# Soft_Latch_11082021.net
KiCad netlist of a schematic drawn in Altium Designer
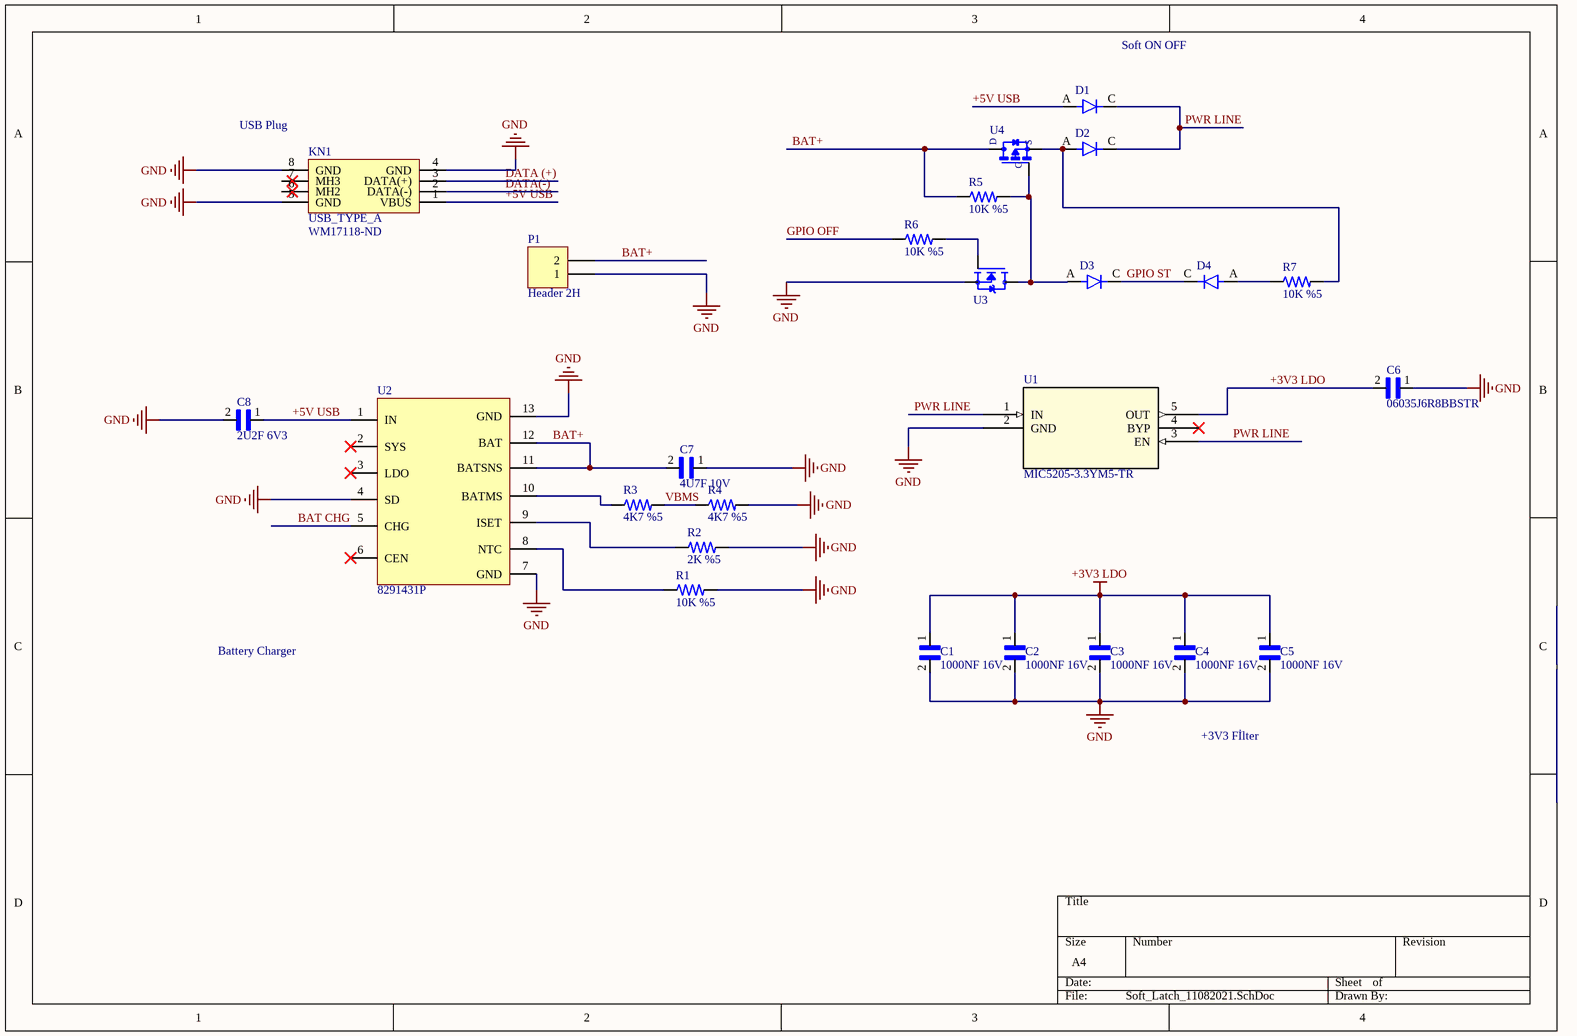
[diagram p0: Soft_Latch_11082021.SchDoc]

(export (version "E")
  (design (tool "Eeschema 10.0.6"))
  (components
    (comp (ref "C1")
      (value "1000NF 16V")
      (footprint "CAP")
      (fields (field (name "MP") "06035J6R8BBSTR"))
      (libsource (lib "Soft_Latch_11082021") (part "06035J6R8BBSTR"))
    )
    (comp (ref "C2")
      (value "1000NF 16V")
      (footprint "CAP")
      (fields (field (name "MP") "06035J6R8BBSTR"))
      (libsource (lib "Soft_Latch_11082021") (part "06035J6R8BBSTR"))
    )
    (comp (ref "C3")
      (value "1000NF 16V")
      (footprint "CAP")
      (fields (field (name "MP") "06035J6R8BBSTR"))
      (libsource (lib "Soft_Latch_11082021") (part "06035J6R8BBSTR"))
    )
    (comp (ref "C4")
      (value "1000NF 16V")
      (footprint "CAP")
      (fields (field (name "MP") "06035J6R8BBSTR"))
      (libsource (lib "Soft_Latch_11082021") (part "06035J6R8BBSTR"))
    )
    (comp (ref "C5")
      (value "1000NF 16V")
      (footprint "CAP")
      (fields (field (name "MP") "06035J6R8BBSTR"))
      (libsource (lib "Soft_Latch_11082021") (part "06035J6R8BBSTR"))
    )
    (comp (ref "C6")
      (value "06035J6R8BBSTR")
      (footprint "CAP")
      (libsource (lib "") (part "06035J6R8BBSTR_1"))
    )
    (comp (ref "C7")
      (value "4U7F 10V")
      (footprint "CAP")
      (fields (field (name "MP") "06035J6R8BBSTR"))
      (libsource (lib "") (part "06035J6R8BBSTR_1"))
    )
    (comp (ref "C8")
      (value "2U2F 6V3")
      (footprint "CAP")
      (fields (field (name "MP") "06035J6R8BBSTR"))
      (libsource (lib "") (part "06035J6R8BBSTR_1"))
    )
    (comp (ref "D1")
      (value "~")
      (footprint "diode")
      (description "Diode Standard 100V 150mA Surface Mount SOD-123")
      (fields (field (name "MP") "1N4148W+") (field (name "MF") "Micro Commercial"))
      (libsource (lib "Soft_Latch_11082021") (part "1N4148WT"))
    )
    (comp (ref "D2")
      (value "~")
      (footprint "diode")
      (description "Diode Standard 100V 150mA Surface Mount SOD-123")
      (fields (field (name "MP") "1N4148W+") (field (name "MF") "Micro Commercial"))
      (libsource (lib "Soft_Latch_11082021") (part "1N4148WT"))
    )
    (comp (ref "D3")
      (value "~")
      (footprint "diode")
      (description "Diode Standard 100V 150mA Surface Mount SOD-123")
      (fields (field (name "MP") "1N4148W+") (field (name "MF") "Micro Commercial"))
      (libsource (lib "Soft_Latch_11082021") (part "1N4148WT"))
    )
    (comp (ref "D4")
      (value "~")
      (footprint "diode")
      (description "Diode Standard 100V 150mA Surface Mount SOD-123")
      (fields (field (name "MP") "1N4148W+") (field (name "MF") "Micro Commercial"))
      (libsource (lib "Soft_Latch_11082021") (part "1N4148WT"))
    )
    (comp (ref "KN1")
      (value "USB_TYPE_A")
      (footprint "USB_TYPE_A")
      (description "Conn USB 2.0 Type A PL 4 POS Solder RA SMD 4 Terminal 1 Port Tray")
      (fields
        (field (name "MANUFACTURER") "Molex")
        (field (name "MANUFACTURER PART NUMBER") "0480371000")
        (field (name "SUPPLIER PART NUMBER 1") "WM17118-ND")
      )
      (libsource (lib "Soft_Latch_11082021") (part "USB_TYPE_A"))
    )
    (comp (ref "P1")
      (value "Header 2H")
      (footprint "HDR1X2H")
      (description "Header, 2-Pin, Right Angle")
      (fields (field (name "PUBLISHER") "Altium Limited"))
      (libsource (lib "Miscellaneous Connectors") (part "Header 2H"))
    )
    (comp (ref "R1")
      (value "10K %5")
      (footprint "RES")
      (description "RES SMD 22K OHM 0.1% 1/16W 0603")
      (fields (field (name "MF") "TE Connectivity") (field (name "MP") "8-1676481-3"))
      (libsource (lib "Soft_Latch_11082021") (part "8-1676481-3"))
    )
    (comp (ref "R2")
      (value "2K %5")
      (footprint "RES")
      (description "RES SMD 22K OHM 0.1% 1/16W 0603")
      (fields (field (name "MF") "TE Connectivity") (field (name "MP") "8-1676481-3"))
      (libsource (lib "Soft_Latch_11082021") (part "8-1676481-3"))
    )
    (comp (ref "R3")
      (value "4K7 %5")
      (footprint "RES")
      (description "RES SMD 22K OHM 0.1% 1/16W 0603")
      (fields (field (name "MF") "TE Connectivity") (field (name "MP") "8-1676481-3"))
      (libsource (lib "Soft_Latch_11082021") (part "8-1676481-3"))
    )
    (comp (ref "R4")
      (value "4K7 %5")
      (footprint "RES")
      (description "RES SMD 22K OHM 0.1% 1/16W 0603")
      (fields (field (name "MF") "TE Connectivity") (field (name "MP") "8-1676481-3"))
      (libsource (lib "Soft_Latch_11082021") (part "8-1676481-3"))
    )
    (comp (ref "R5")
      (value "10K %5")
      (footprint "RES")
      (description "RES SMD 22K OHM 0.1% 1/16W 0603")
      (fields (field (name "MF") "TE Connectivity") (field (name "MP") "8-1676481-3"))
      (libsource (lib "Soft_Latch_11082021") (part "8-1676481-3"))
    )
    (comp (ref "R6")
      (value "10K %5")
      (footprint "RES")
      (description "RES SMD 22K OHM 0.1% 1/16W 0603")
      (fields (field (name "MF") "TE Connectivity") (field (name "MP") "8-1676481-3"))
      (libsource (lib "Soft_Latch_11082021") (part "8-1676481-3"))
    )
    (comp (ref "R7")
      (value "10K %5")
      (footprint "RES")
      (description "RES SMD 22K OHM 0.1% 1/16W 0603")
      (fields (field (name "MF") "TE Connectivity") (field (name "MP") "8-1676481-3"))
      (libsource (lib "Soft_Latch_11082021") (part "8-1676481-3"))
    )
    (comp (ref "U1")
      (value "MIC5205-3.3YM5-TR")
      (footprint "SOT-23-5_MC_MCH-M")
      (description "No Description Available")
      (fields (field (name "COPYRIGHT") "Copyright (C) 2021 Ultra Librarian. All rights reserved."))
      (libsource (lib "Soft_Latch_11082021") (part "MIC5205-3.3YM5-TR"))
    )
    (comp (ref "U2")
      (value "STNS01")
      (footprint "STNS01")
      (description "IC LI-ION BATT CHARGER LDO 12DFN")
      (fields
        (field (name "MANUFACTURER") "STMicroelectronics")
        (field (name "MANUFACTURER PART NUMBER") "STNS01PUR")
        (field (name "SUPPLIER PART NUMBER 1") "8291431P")
      )
      (libsource (lib "Soft_Latch_11082021") (part "STNS01"))
    )
    (comp (ref "U3")
      (value "~")
      (footprint "n-mosfet")
      (description "N-Channel 60V 280mA (Ta) 350mW (Ta) Surface Mount SOT-23-3 (TO-236)")
      (fields (field (name "MP") "2N7002") (field (name "MF") "ON Semiconductor"))
      (libsource (lib "Soft_Latch_11082021") (part "2N7002"))
    )
    (comp (ref "U4")
      (value "~")
      (footprint "p-Mosfet")
      (description "P-Channel 30V 1.3A _Ta_ 500mW _Ta_ Surface Mount SuperSOT-3")
      (fields (field (name "MF") "ON Semiconductor") (field (name "MP") "FDN352AP"))
      (libsource (lib "Soft_Latch_11082021") (part "FDN352AP"))
    )
  )
  (nets
    (net (code "1") (name "+3V3 LDO") (class "Default")
      (node (ref "C1") (pin "1") (pinfunction "1_1") (pintype "passive"))
      (node (ref "C2") (pin "1") (pinfunction "1_1") (pintype "passive"))
      (node (ref "C3") (pin "1") (pinfunction "1_1") (pintype "passive"))
      (node (ref "C4") (pin "1") (pinfunction "1_1") (pintype "passive"))
      (node (ref "C5") (pin "1") (pinfunction "1_1") (pintype "passive"))
      (node (ref "C6") (pin "2") (pinfunction "2_2") (pintype "passive"))
      (node (ref "U1") (pin "5") (pinfunction "OUT_5") (pintype "output"))
    )
    (net (code "2") (name "/+5V USB") (class "Default")
      (node (ref "C8") (pin "1") (pinfunction "1_1") (pintype "passive"))
      (node (ref "D1") (pin "A") (pinfunction "A_A") (pintype "passive"))
      (node (ref "KN1") (pin "1") (pinfunction "VBUS_1") (pintype "passive"))
      (node (ref "U2") (pin "1") (pinfunction "IN_1") (pintype "passive"))
    )
    (net (code "3") (name "/BAT CHG") (class "Default")
      (node (ref "U2") (pin "5") (pinfunction "CHG_5") (pintype "passive"))
    )
    (net (code "4") (name "/BAT+") (class "Default")
      (node (ref "C7") (pin "2") (pinfunction "2_2") (pintype "passive"))
      (node (ref "P1") (pin "2") (pinfunction "2_2") (pintype "passive"))
      (node (ref "R5") (pin "1") (pinfunction "1_1") (pintype "passive"))
      (node (ref "U2") (pin "11") (pinfunction "BATSNS_11") (pintype "passive"))
      (node (ref "U2") (pin "12") (pinfunction "BAT_12") (pintype "passive"))
      (node (ref "U4") (pin "3") (pinfunction "D_3") (pintype "passive"))
    )
    (net (code "5") (name "/DATA (+)") (class "Default")
      (node (ref "KN1") (pin "3") (pinfunction "DATA(+)_3") (pintype "passive"))
    )
    (net (code "6") (name "/DATA(-)") (class "Default")
      (node (ref "KN1") (pin "2") (pinfunction "DATA(-)_2") (pintype "passive"))
    )
    (net (code "7") (name "/GPIO OFF") (class "Default")
      (node (ref "R6") (pin "1") (pinfunction "1_1") (pintype "passive"))
    )
    (net (code "8") (name "/GPIO ST") (class "Default")
      (node (ref "D3") (pin "C") (pinfunction "C_C") (pintype "passive"))
      (node (ref "D4") (pin "C") (pinfunction "C_C") (pintype "passive"))
    )
    (net (code "9") (name "/PWR LINE") (class "Default")
      (node (ref "D1") (pin "C") (pinfunction "C_C") (pintype "passive"))
      (node (ref "D2") (pin "C") (pinfunction "C_C") (pintype "passive"))
      (node (ref "U1") (pin "1") (pinfunction "IN_1") (pintype "input"))
      (node (ref "U1") (pin "3") (pinfunction "EN_3") (pintype "input"))
    )
    (net (code "10") (name "/VBMS") (class "Default")
      (node (ref "R3") (pin "2") (pinfunction "2_2") (pintype "passive"))
      (node (ref "R4") (pin "1") (pinfunction "1_1") (pintype "passive"))
    )
    (net (code "11") (name "GND") (class "Default")
      (node (ref "C1") (pin "2") (pinfunction "2_2") (pintype "passive"))
      (node (ref "C2") (pin "2") (pinfunction "2_2") (pintype "passive"))
      (node (ref "C3") (pin "2") (pinfunction "2_2") (pintype "passive"))
      (node (ref "C4") (pin "2") (pinfunction "2_2") (pintype "passive"))
      (node (ref "C5") (pin "2") (pinfunction "2_2") (pintype "passive"))
      (node (ref "C6") (pin "1") (pinfunction "1_1") (pintype "passive"))
      (node (ref "C7") (pin "1") (pinfunction "1_1") (pintype "passive"))
      (node (ref "C8") (pin "2") (pinfunction "2_2") (pintype "passive"))
      (node (ref "KN1") (pin "4") (pinfunction "GND_4") (pintype "passive"))
      (node (ref "KN1") (pin "5") (pinfunction "GND_5") (pintype "passive"))
      (node (ref "KN1") (pin "8") (pinfunction "GND_8") (pintype "passive"))
      (node (ref "P1") (pin "1") (pinfunction "1_1") (pintype "passive"))
      (node (ref "R1") (pin "2") (pinfunction "2_2") (pintype "passive"))
      (node (ref "R2") (pin "2") (pinfunction "2_2") (pintype "passive"))
      (node (ref "R4") (pin "2") (pinfunction "2_2") (pintype "passive"))
      (node (ref "U1") (pin "2") (pinfunction "GND_2") (pintype "power_in"))
      (node (ref "U2") (pin "13") (pinfunction "GND_13") (pintype "passive"))
      (node (ref "U2") (pin "4") (pinfunction "SD_4") (pintype "passive"))
      (node (ref "U2") (pin "7") (pinfunction "GND_7") (pintype "passive"))
      (node (ref "U3") (pin "2") (pinfunction "S_2") (pintype "passive"))
    )
    (net (code "12") (name "Net-(D4-PadA)") (class "Default")
      (node (ref "D4") (pin "A") (pinfunction "A_A") (pintype "passive"))
      (node (ref "R7") (pin "1") (pinfunction "1_1") (pintype "passive"))
    )
    (net (code "13") (name "Net-(U2-BATMS)") (class "Default")
      (node (ref "R3") (pin "1") (pinfunction "1_1") (pintype "passive"))
      (node (ref "U2") (pin "10") (pinfunction "BATMS_10") (pintype "passive"))
    )
    (net (code "14") (name "Net-(U2-ISET)") (class "Default")
      (node (ref "R2") (pin "1") (pinfunction "1_1") (pintype "passive"))
      (node (ref "U2") (pin "9") (pinfunction "ISET_9") (pintype "passive"))
    )
    (net (code "15") (name "Net-(U2-NTC)") (class "Default")
      (node (ref "R1") (pin "1") (pinfunction "1_1") (pintype "passive"))
      (node (ref "U2") (pin "8") (pinfunction "NTC_8") (pintype "passive"))
    )
    (net (code "16") (name "Net-(U3-D)") (class "Default")
      (node (ref "D3") (pin "A") (pinfunction "A_A") (pintype "passive"))
      (node (ref "R5") (pin "2") (pinfunction "2_2") (pintype "passive"))
      (node (ref "U3") (pin "3") (pinfunction "D_3") (pintype "passive"))
      (node (ref "U4") (pin "1") (pinfunction "G_1") (pintype "passive"))
    )
    (net (code "17") (name "Net-(U3-G)") (class "Default")
      (node (ref "R6") (pin "2") (pinfunction "2_2") (pintype "passive"))
      (node (ref "U3") (pin "1") (pinfunction "G_1") (pintype "passive"))
    )
    (net (code "18") (name "Net-(U4-S)") (class "Default")
      (node (ref "D2") (pin "A") (pinfunction "A_A") (pintype "passive"))
      (node (ref "R7") (pin "2") (pinfunction "2_2") (pintype "passive"))
      (node (ref "U4") (pin "2") (pinfunction "S_2") (pintype "passive"))
    )
    (net (code "19") (name "unconnected-(KN1-MH2-Pad6)") (class "Default")
      (node (ref "KN1") (pin "6") (pinfunction "MH2_6") (pintype "passive"))
    )
    (net (code "20") (name "unconnected-(KN1-MH3-Pad7)") (class "Default")
      (node (ref "KN1") (pin "7") (pinfunction "MH3_7") (pintype "passive"))
    )
    (net (code "21") (name "unconnected-(U1-BYP-Pad4)") (class "Default")
      (node (ref "U1") (pin "4") (pinfunction "BYP_4") (pintype "passive+no_connect"))
    )
    (net (code "22") (name "unconnected-(U2-CEN-Pad6)") (class "Default")
      (node (ref "U2") (pin "6") (pinfunction "CEN_6") (pintype "passive+no_connect"))
    )
    (net (code "23") (name "unconnected-(U2-LDO-Pad3)") (class "Default")
      (node (ref "U2") (pin "3") (pinfunction "LDO_3") (pintype "passive+no_connect"))
    )
    (net (code "24") (name "unconnected-(U2-SYS-Pad2)") (class "Default")
      (node (ref "U2") (pin "2") (pinfunction "SYS_2") (pintype "passive+no_connect"))
    )
  )
)
